# ICS40300-Silicon-Mic_Rev-A_s_x.net
KiCad netlist of a schematic drawn in EAGLE
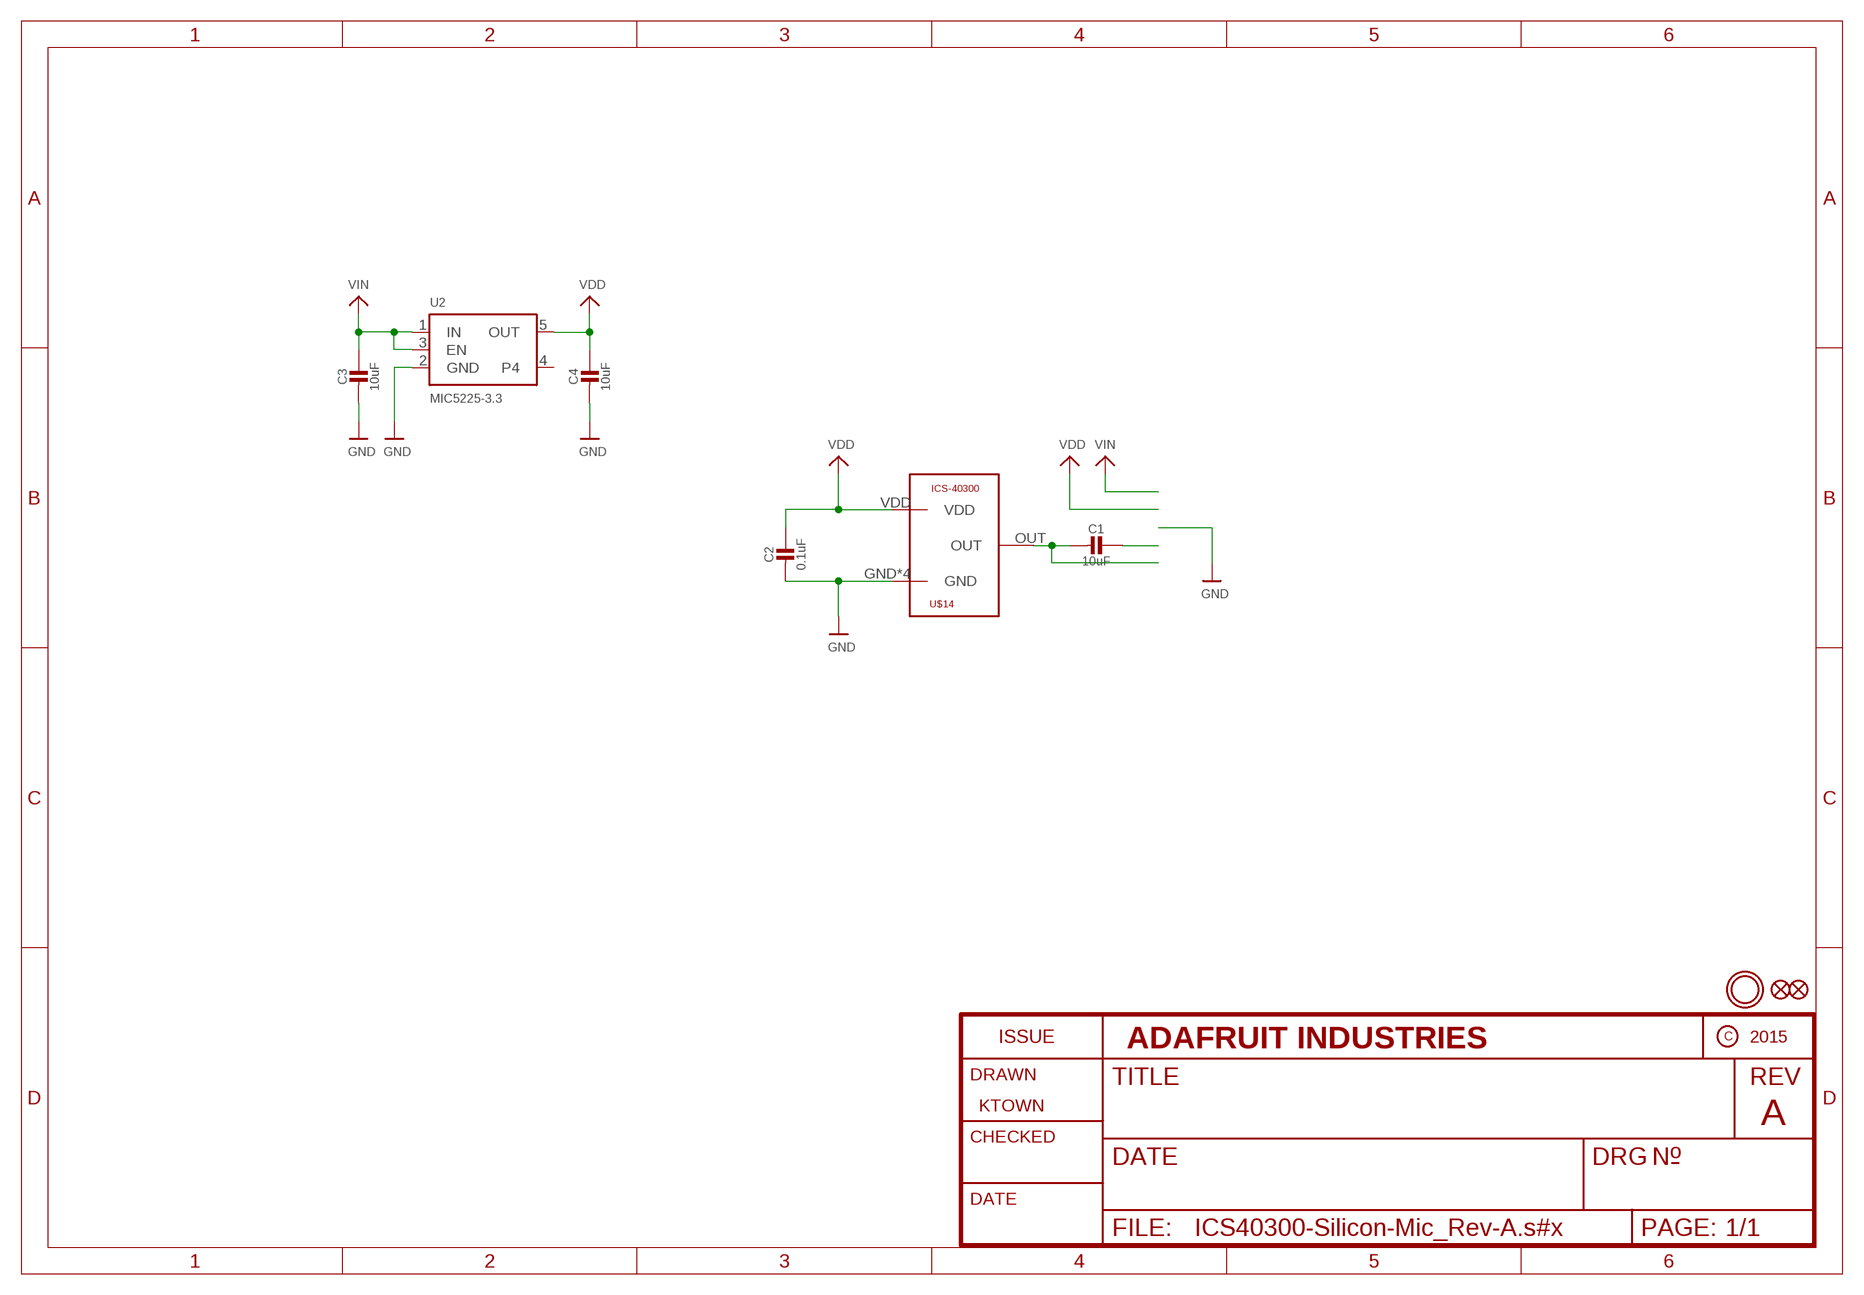
[diagram p0: schematic, sheet 1]

(export (version "E")
  (design (tool "Eeschema 10.0.6"))
  (components
    (comp (ref "C1")
      (value "10uF")
      (footprint "eagle-import:0805-NO")
      (libsource (lib "eagle-import") (part "CAP_CERAMIC0805-NOOUTLINE"))
    )
    (comp (ref "C2")
      (value "0.1uF")
      (footprint "eagle-import:0805-NO")
      (libsource (lib "eagle-import") (part "CAP_CERAMIC0805-NOOUTLINE"))
    )
    (comp (ref "C3")
      (value "10uF")
      (footprint "eagle-import:0805-NO")
      (libsource (lib "eagle-import") (part "CAP_CERAMIC0805-NOOUTLINE"))
    )
    (comp (ref "C4")
      (value "10uF")
      (footprint "eagle-import:0805-NO")
      (libsource (lib "eagle-import") (part "CAP_CERAMIC0805-NOOUTLINE"))
    )
    (comp (ref "FID1")
      (value "FIDUCIAL\"\"")
      (footprint "eagle-import:FIDUCIAL_1MM")
      (libsource (lib "eagle-import") (part "FIDUCIAL{dblquote}{dblquote}"))
    )
    (comp (ref "FID2")
      (value "FIDUCIAL\"\"")
      (footprint "eagle-import:FIDUCIAL_1MM")
      (libsource (lib "eagle-import") (part "FIDUCIAL{dblquote}{dblquote}"))
    )
    (comp (ref "U$12")
      (value "MOUNTINGHOLE2.5")
      (footprint "eagle-import:MOUNTINGHOLE_2.5_PLATED")
      (libsource (lib "eagle-import") (part "MOUNTINGHOLE2.5"))
    )
    (comp (ref "U$14")
      (value "ICS-40300")
      (footprint "eagle-import:ICS-40300")
      (libsource (lib "eagle-import") (part "ICS-40300"))
    )
    (comp (ref "U2")
      (value "MIC5225-3.3")
      (footprint "eagle-import:SOT23-5")
      (libsource (lib "eagle-import") (part "VREG_SOT23-5"))
    )
  )
  (nets
    (net (code "1") (name "GND") (class "Default")
      (node (ref "C2") (pin "2") (pinfunction "2_2") (pintype "passive"))
      (node (ref "C3") (pin "2") (pinfunction "2_2") (pintype "passive"))
      (node (ref "C4") (pin "2") (pinfunction "2_2") (pintype "passive"))
      (node (ref "U$14") (pin "GND") (pinfunction "GND_GND") (pintype "bidirectional"))
      (node (ref "U$14") (pin "GND1") (pinfunction "GND_GND1") (pintype "bidirectional"))
      (node (ref "U$14") (pin "GND2") (pinfunction "GND_GND2") (pintype "bidirectional"))
      (node (ref "U$14") (pin "GND3") (pinfunction "GND_GND3") (pintype "bidirectional"))
      (node (ref "U2") (pin "2") (pinfunction "GND_2") (pintype "power_in"))
    )
    (net (code "2") (name "Net-(C1-Pad2)") (class "Default")
      (node (ref "C1") (pin "2") (pinfunction "2_2") (pintype "passive"))
      (node (ref "U$14") (pin "OUT") (pinfunction "OUT_OUT") (pintype "bidirectional"))
    )
    (net (code "3") (name "VDD") (class "Default")
      (node (ref "C2") (pin "1") (pinfunction "1_1") (pintype "passive"))
      (node (ref "C4") (pin "1") (pinfunction "1_1") (pintype "passive"))
      (node (ref "U$14") (pin "VDD") (pinfunction "VDD_VDD") (pintype "bidirectional"))
      (node (ref "U2") (pin "5") (pinfunction "OUT_5") (pintype "power_in"))
    )
    (net (code "4") (name "VIN") (class "Default")
      (node (ref "C3") (pin "1") (pinfunction "1_1") (pintype "passive"))
      (node (ref "U2") (pin "1") (pinfunction "IN_1") (pintype "power_in"))
      (node (ref "U2") (pin "3") (pinfunction "EN_3") (pintype "input"))
    )
    (net (code "5") (name "unconnected-(C1-Pad1)") (class "Default")
      (node (ref "C1") (pin "1") (pinfunction "1_1") (pintype "passive"))
    )
    (net (code "6") (name "unconnected-(U2-P4-Pad4)") (class "Default")
      (node (ref "U2") (pin "4") (pinfunction "P4_4") (pintype "bidirectional"))
    )
  )
)
